# teensyMotors02_upSwitch.net
KiCad netlist of a schematic drawn in EAGLE
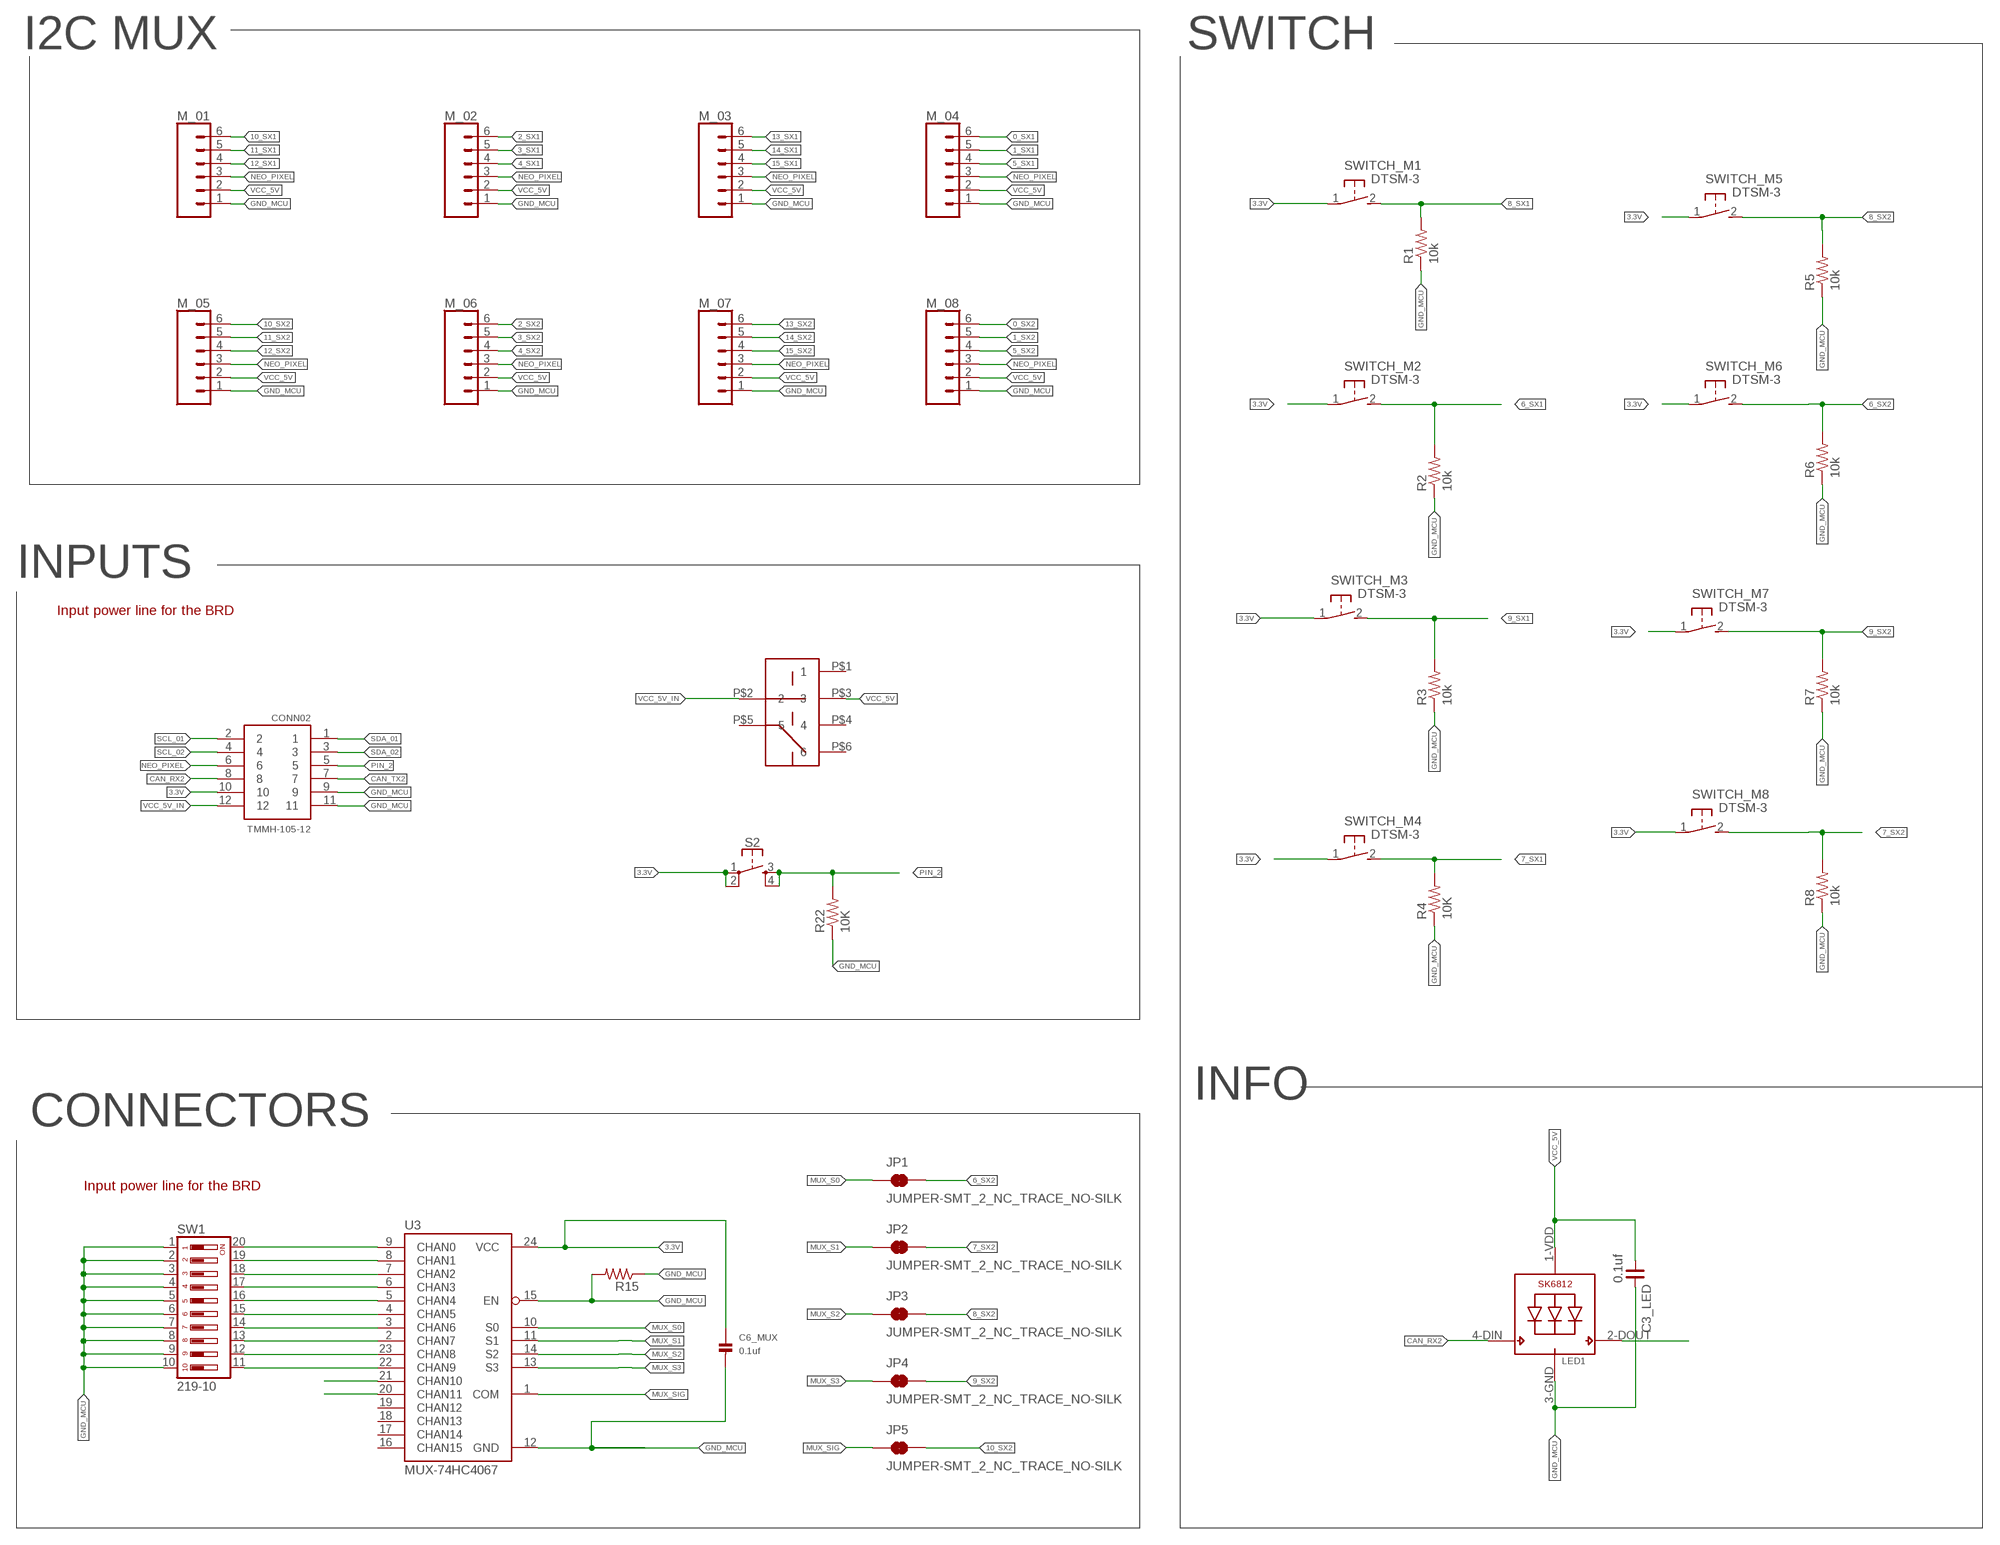
[diagram p0: schematic, sheet 1, part 1 of 2]
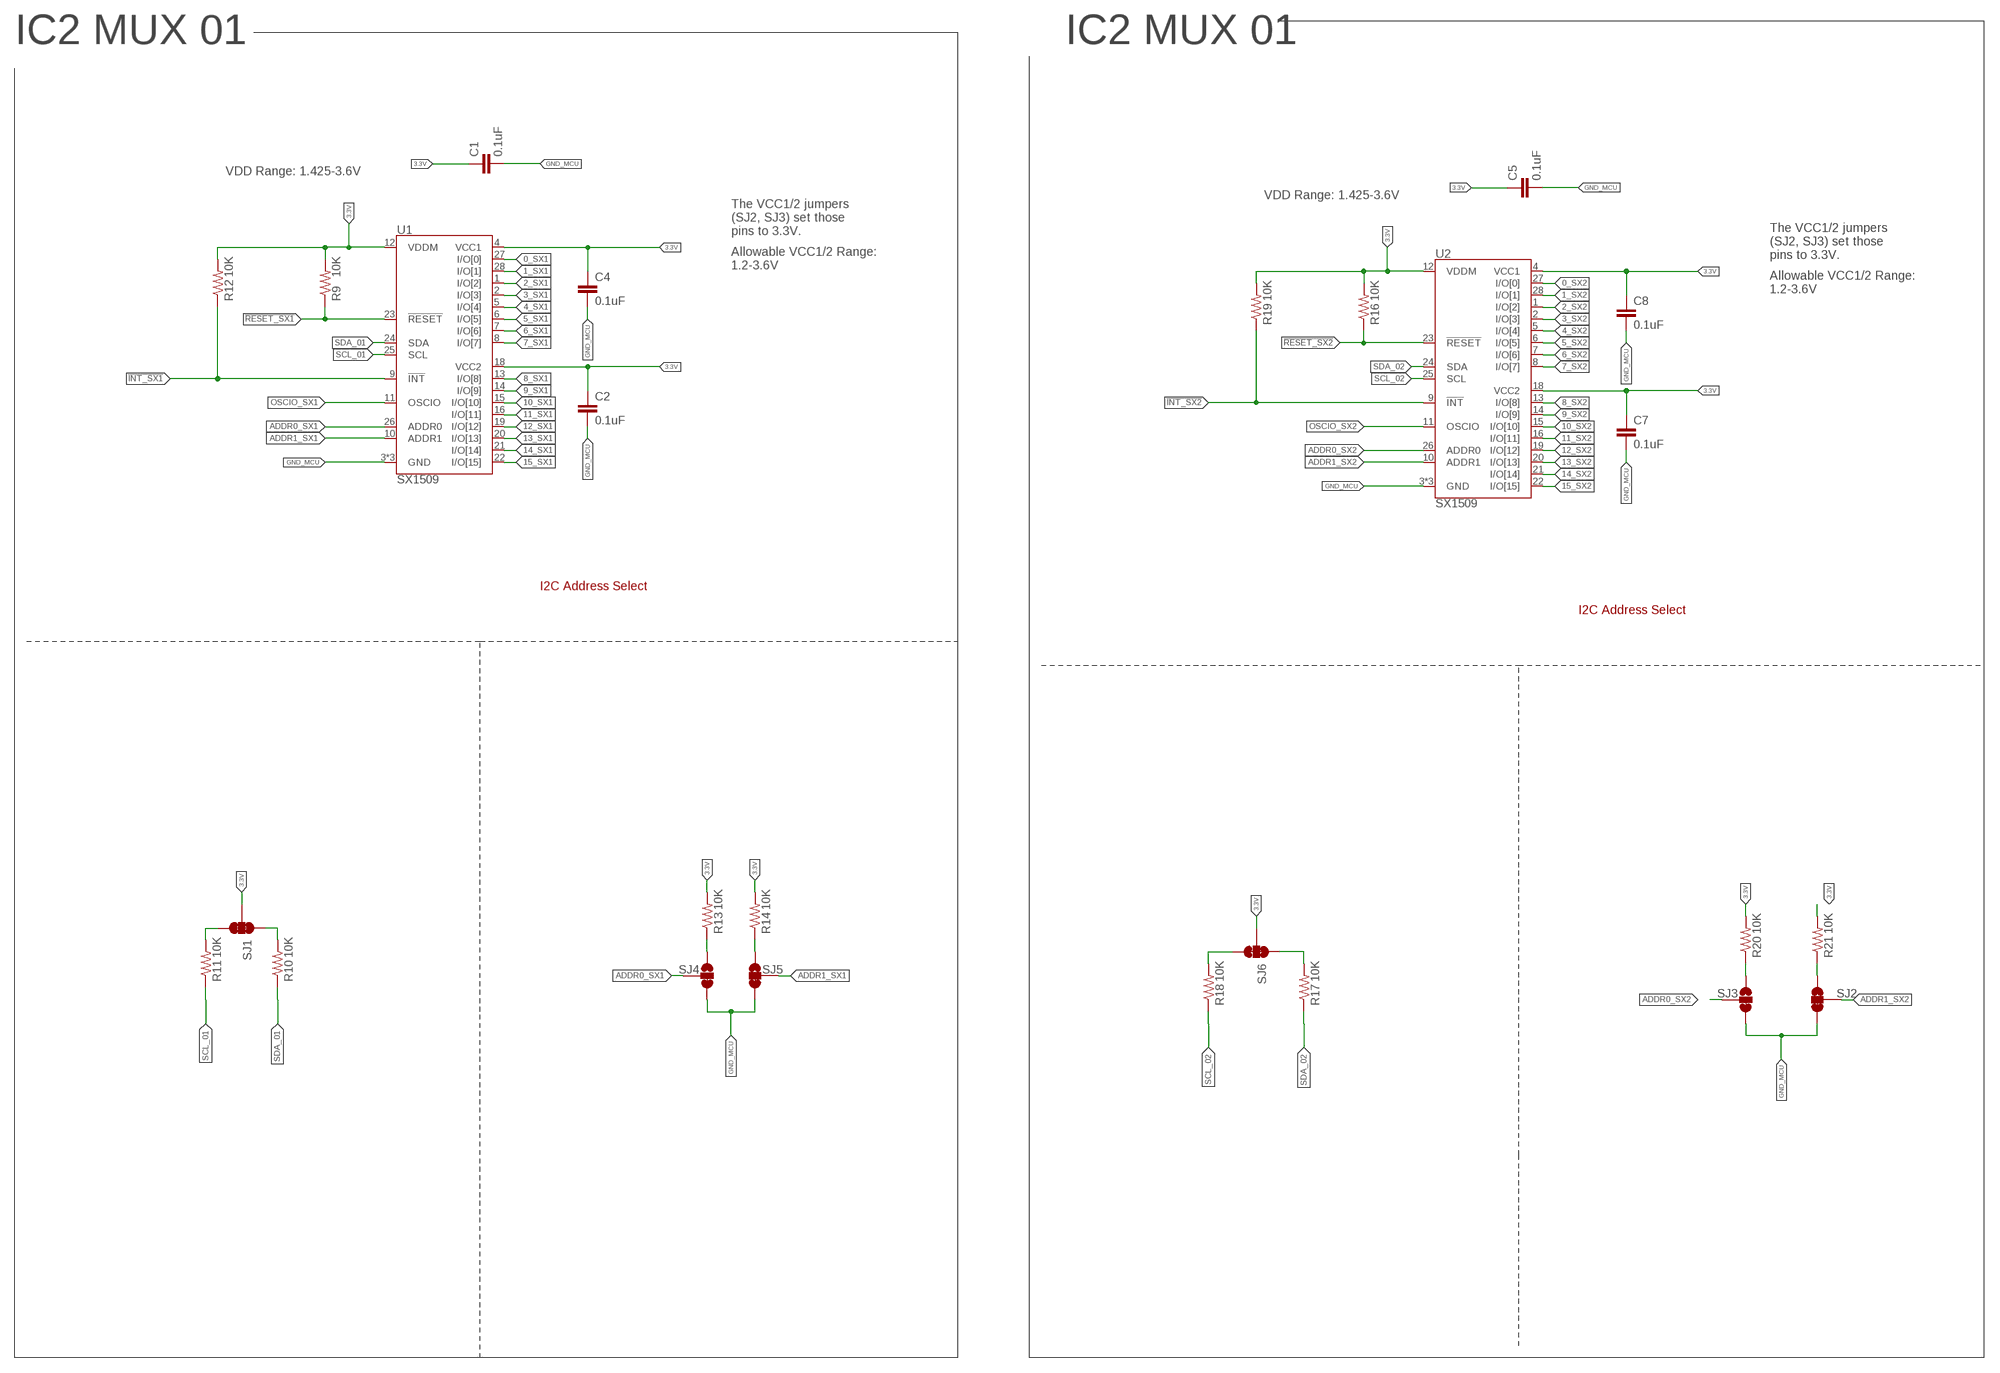
[diagram p1: schematic, sheet 1, part 2 of 2]

(export (version "E")
  (design (tool "Eeschema 10.0.6"))
  (components
    (comp (ref "C1")
      (value "0.1uF")
      (footprint "eagle-import:0603-CAP")
      (libsource (lib "eagle-import") (part "0.1UF-25V(+80/-20%)(0603)"))
    )
    (comp (ref "C2")
      (value "0.1uF")
      (footprint "eagle-import:0603-CAP")
      (libsource (lib "eagle-import") (part "0.1UF-25V(+80/-20%)(0603)"))
    )
    (comp (ref "C3_LED")
      (value "0.1uf")
      (footprint "eagle-import:C0805")
      (libsource (lib "eagle-import") (part "C_0805"))
    )
    (comp (ref "C4")
      (value "0.1uF")
      (footprint "eagle-import:0603-CAP")
      (libsource (lib "eagle-import") (part "0.1UF-25V(+80/-20%)(0603)"))
    )
    (comp (ref "C5")
      (value "0.1uF")
      (footprint "eagle-import:0603-CAP")
      (libsource (lib "eagle-import") (part "0.1UF-25V(+80/-20%)(0603)"))
    )
    (comp (ref "C6_MUX")
      (value "0.1uf")
      (footprint "eagle-import:0805")
      (libsource (lib "eagle-import") (part "CAP_CERAMIC0805"))
    )
    (comp (ref "C7")
      (value "0.1uF")
      (footprint "eagle-import:0603-CAP")
      (libsource (lib "eagle-import") (part "0.1UF-25V(+80/-20%)(0603)"))
    )
    (comp (ref "C8")
      (value "0.1uF")
      (footprint "eagle-import:0603-CAP")
      (libsource (lib "eagle-import") (part "0.1UF-25V(+80/-20%)(0603)"))
    )
    (comp (ref "CONN02")
      (value "TMMH-105-12")
      (footprint "eagle-import:TMMH-105-12")
      (libsource (lib "eagle-import") (part "TMMH-105-12"))
    )
    (comp (ref "JP1")
      (value "JUMPER-SMT_2_NC_TRACE_NO-SILK")
      (footprint "eagle-import:SMT-JUMPER_2_NC_TRACE_NO-SILK")
      (libsource (lib "eagle-import") (part "JUMPER-SMT_2_NC_TRACE_NO-SILK"))
    )
    (comp (ref "JP2")
      (value "JUMPER-SMT_2_NC_TRACE_NO-SILK")
      (footprint "eagle-import:SMT-JUMPER_2_NC_TRACE_NO-SILK")
      (libsource (lib "eagle-import") (part "JUMPER-SMT_2_NC_TRACE_NO-SILK"))
    )
    (comp (ref "JP3")
      (value "JUMPER-SMT_2_NC_TRACE_NO-SILK")
      (footprint "eagle-import:SMT-JUMPER_2_NC_TRACE_NO-SILK")
      (libsource (lib "eagle-import") (part "JUMPER-SMT_2_NC_TRACE_NO-SILK"))
    )
    (comp (ref "JP4")
      (value "JUMPER-SMT_2_NC_TRACE_NO-SILK")
      (footprint "eagle-import:SMT-JUMPER_2_NC_TRACE_NO-SILK")
      (libsource (lib "eagle-import") (part "JUMPER-SMT_2_NC_TRACE_NO-SILK"))
    )
    (comp (ref "JP5")
      (value "JUMPER-SMT_2_NC_TRACE_NO-SILK")
      (footprint "eagle-import:SMT-JUMPER_2_NC_TRACE_NO-SILK")
      (libsource (lib "eagle-import") (part "JUMPER-SMT_2_NC_TRACE_NO-SILK"))
    )
    (comp (ref "LED1")
      (value "SK6812_5050N")
      (footprint "eagle-import:LED5050_N")
      (libsource (lib "eagle-import") (part "SK6812_5050N"))
    )
    (comp (ref "M_01")
      (value "CONN_06SMD-1MM")
      (footprint "eagle-import:1X06-1MM")
      (libsource (lib "eagle-import") (part "CONN_06SMD-1MM"))
    )
    (comp (ref "M_02")
      (value "CONN_06SMD-1MM")
      (footprint "eagle-import:1X06-1MM")
      (libsource (lib "eagle-import") (part "CONN_06SMD-1MM"))
    )
    (comp (ref "M_03")
      (value "CONN_06SMD-1MM")
      (footprint "eagle-import:1X06-1MM")
      (libsource (lib "eagle-import") (part "CONN_06SMD-1MM"))
    )
    (comp (ref "M_04")
      (value "CONN_06SMD-1MM")
      (footprint "eagle-import:1X06-1MM")
      (libsource (lib "eagle-import") (part "CONN_06SMD-1MM"))
    )
    (comp (ref "M_05")
      (value "CONN_06SMD-1MM")
      (footprint "eagle-import:1X06-1MM")
      (libsource (lib "eagle-import") (part "CONN_06SMD-1MM"))
    )
    (comp (ref "M_06")
      (value "CONN_06SMD-1MM")
      (footprint "eagle-import:1X06-1MM")
      (libsource (lib "eagle-import") (part "CONN_06SMD-1MM"))
    )
    (comp (ref "M_07")
      (value "CONN_06SMD-1MM")
      (footprint "eagle-import:1X06-1MM")
      (libsource (lib "eagle-import") (part "CONN_06SMD-1MM"))
    )
    (comp (ref "M_08")
      (value "CONN_06SMD-1MM")
      (footprint "eagle-import:1X06-1MM")
      (libsource (lib "eagle-import") (part "CONN_06SMD-1MM"))
    )
    (comp (ref "R1")
      (value "10k")
      (footprint "eagle-import:M0805")
      (libsource (lib "eagle-import") (part "R-US_M0805"))
    )
    (comp (ref "R2")
      (value "10k")
      (footprint "eagle-import:M0805")
      (libsource (lib "eagle-import") (part "R-US_M0805"))
    )
    (comp (ref "R3")
      (value "10k")
      (footprint "eagle-import:M0805")
      (libsource (lib "eagle-import") (part "R-US_M0805"))
    )
    (comp (ref "R4")
      (value "10K")
      (footprint "eagle-import:M0805")
      (libsource (lib "eagle-import") (part "R-US_M0805"))
    )
    (comp (ref "R5")
      (value "10k")
      (footprint "eagle-import:M0805")
      (libsource (lib "eagle-import") (part "R-US_M0805"))
    )
    (comp (ref "R6")
      (value "10k")
      (footprint "eagle-import:M0805")
      (libsource (lib "eagle-import") (part "R-US_M0805"))
    )
    (comp (ref "R7")
      (value "10k")
      (footprint "eagle-import:M0805")
      (libsource (lib "eagle-import") (part "R-US_M0805"))
    )
    (comp (ref "R8")
      (value "10k")
      (footprint "eagle-import:M0805")
      (libsource (lib "eagle-import") (part "R-US_M0805"))
    )
    (comp (ref "R9")
      (value "10K")
      (footprint "eagle-import:0603-RES")
      (libsource (lib "eagle-import") (part "10KOHM-1/10W-1%(0603)0603"))
    )
    (comp (ref "R10")
      (value "10K")
      (footprint "eagle-import:0603-RES")
      (libsource (lib "eagle-import") (part "10KOHM-1/10W-1%(0603)0603"))
    )
    (comp (ref "R11")
      (value "10K")
      (footprint "eagle-import:0603-RES")
      (libsource (lib "eagle-import") (part "10KOHM-1/10W-1%(0603)0603"))
    )
    (comp (ref "R12")
      (value "10K")
      (footprint "eagle-import:0603-RES")
      (libsource (lib "eagle-import") (part "10KOHM-1/10W-1%(0603)0603"))
    )
    (comp (ref "R13")
      (value "10K")
      (footprint "eagle-import:0603-RES")
      (libsource (lib "eagle-import") (part "10KOHM-1/10W-1%(0603)0603"))
    )
    (comp (ref "R14")
      (value "10K")
      (footprint "eagle-import:0603-RES")
      (libsource (lib "eagle-import") (part "10KOHM-1/10W-1%(0603)0603"))
    )
    (comp (ref "R15")
      (value "R-US_M0805")
      (footprint "eagle-import:M0805")
      (libsource (lib "eagle-import") (part "R-US_M0805"))
    )
    (comp (ref "R16")
      (value "10K")
      (footprint "eagle-import:0603-RES")
      (libsource (lib "eagle-import") (part "10KOHM-1/10W-1%(0603)0603"))
    )
    (comp (ref "R17")
      (value "10K")
      (footprint "eagle-import:0603-RES")
      (libsource (lib "eagle-import") (part "10KOHM-1/10W-1%(0603)0603"))
    )
    (comp (ref "R18")
      (value "10K")
      (footprint "eagle-import:0603-RES")
      (libsource (lib "eagle-import") (part "10KOHM-1/10W-1%(0603)0603"))
    )
    (comp (ref "R19")
      (value "10K")
      (footprint "eagle-import:0603-RES")
      (libsource (lib "eagle-import") (part "10KOHM-1/10W-1%(0603)0603"))
    )
    (comp (ref "R20")
      (value "10K")
      (footprint "eagle-import:0603-RES")
      (libsource (lib "eagle-import") (part "10KOHM-1/10W-1%(0603)0603"))
    )
    (comp (ref "R21")
      (value "10K")
      (footprint "eagle-import:0603-RES")
      (libsource (lib "eagle-import") (part "10KOHM-1/10W-1%(0603)0603"))
    )
    (comp (ref "R22")
      (value "10K")
      (footprint "eagle-import:M0805")
      (libsource (lib "eagle-import") (part "R-US_M0805"))
    )
    (comp (ref "S2")
      (value "MOMENTARY-SWITCH-SPST-2-SMD-5.2MM")
      (footprint "eagle-import:TACTILE_SWITCH_SMD_5.2MM")
      (libsource (lib "eagle-import") (part "MOMENTARY-SWITCH-SPST-2-SMD-5.2MM"))
    )
    (comp (ref "SJ1")
      (value "JUMPER-PAD-3-NC_BY_TRACE")
      (footprint "eagle-import:PAD-JUMPER-3-3OF3_NC_BY_TRACE_YES_SILK_FULL_BOX")
      (libsource (lib "eagle-import") (part "JUMPER-PAD-3-NC_BY_TRACE"))
    )
    (comp (ref "SJ2")
      (value "JUMPER-PAD-3-2OF3_NC_BY_TRACE_SMALL")
      (footprint "eagle-import:PAD-JUMPER-3-2OF3_NC_BY_TRACE_YES_SILK_FULL_BOX")
      (libsource (lib "eagle-import") (part "JUMPER-PAD-3-2OF3_NC_BY_TRACE_SMALL"))
    )
    (comp (ref "SJ3")
      (value "JUMPER-PAD-3-2OF3_NC_BY_TRACE_SMALL")
      (footprint "eagle-import:PAD-JUMPER-3-2OF3_NC_BY_TRACE_YES_SILK_FULL_BOX")
      (libsource (lib "eagle-import") (part "JUMPER-PAD-3-2OF3_NC_BY_TRACE_SMALL"))
    )
    (comp (ref "SJ4")
      (value "JUMPER-PAD-3-2OF3_NC_BY_TRACE_SMALL")
      (footprint "eagle-import:PAD-JUMPER-3-2OF3_NC_BY_TRACE_YES_SILK_FULL_BOX")
      (libsource (lib "eagle-import") (part "JUMPER-PAD-3-2OF3_NC_BY_TRACE_SMALL"))
    )
    (comp (ref "SJ5")
      (value "JUMPER-PAD-3-2OF3_NC_BY_TRACE_SMALL")
      (footprint "eagle-import:PAD-JUMPER-3-2OF3_NC_BY_TRACE_YES_SILK_FULL_BOX")
      (libsource (lib "eagle-import") (part "JUMPER-PAD-3-2OF3_NC_BY_TRACE_SMALL"))
    )
    (comp (ref "SJ6")
      (value "JUMPER-PAD-3-NC_BY_TRACE")
      (footprint "eagle-import:PAD-JUMPER-3-3OF3_NC_BY_TRACE_YES_SILK_FULL_BOX")
      (libsource (lib "eagle-import") (part "JUMPER-PAD-3-NC_BY_TRACE"))
    )
    (comp (ref "SW1")
      (value "219-10")
      (footprint "eagle-import:CTS-219-10")
      (fields (field (name "MF") "SLI (CML/IDI)") (field (name "MPN") "219-10PK"))
      (libsource (lib "eagle-import") (part "219-10"))
    )
    (comp (ref "SWITCH_M1")
      (value "DTSM-3")
      (footprint "eagle-import:DTSM-3")
      (libsource (lib "eagle-import") (part "DTSM-3"))
    )
    (comp (ref "SWITCH_M2")
      (value "DTSM-3")
      (footprint "eagle-import:DTSM-3")
      (libsource (lib "eagle-import") (part "DTSM-3"))
    )
    (comp (ref "SWITCH_M3")
      (value "DTSM-3")
      (footprint "eagle-import:DTSM-3")
      (libsource (lib "eagle-import") (part "DTSM-3"))
    )
    (comp (ref "SWITCH_M4")
      (value "DTSM-3")
      (footprint "eagle-import:DTSM-3")
      (libsource (lib "eagle-import") (part "DTSM-3"))
    )
    (comp (ref "SWITCH_M5")
      (value "DTSM-3")
      (footprint "eagle-import:DTSM-3")
      (libsource (lib "eagle-import") (part "DTSM-3"))
    )
    (comp (ref "SWITCH_M6")
      (value "DTSM-3")
      (footprint "eagle-import:DTSM-3")
      (libsource (lib "eagle-import") (part "DTSM-3"))
    )
    (comp (ref "SWITCH_M7")
      (value "DTSM-3")
      (footprint "eagle-import:DTSM-3")
      (libsource (lib "eagle-import") (part "DTSM-3"))
    )
    (comp (ref "SWITCH_M8")
      (value "DTSM-3")
      (footprint "eagle-import:DTSM-3")
      (libsource (lib "eagle-import") (part "DTSM-3"))
    )
    (comp (ref "U$1")
      (value "MFS201N－9－Z")
      (footprint "eagle-import:MFS201N－9－Z")
      (libsource (lib "eagle-import") (part "MFS201N－9－Z"))
    )
    (comp (ref "U1")
      (value "SX1509")
      (footprint "eagle-import:QFN-28")
      (libsource (lib "eagle-import") (part "SX1509"))
    )
    (comp (ref "U2")
      (value "SX1509")
      (footprint "eagle-import:QFN-28")
      (libsource (lib "eagle-import") (part "SX1509"))
    )
    (comp (ref "U3")
      (value "MUX-74HC4067")
      (footprint "eagle-import:SSOP24")
      (libsource (lib "eagle-import") (part "MUX-74HC4067SMD"))
    )
  )
  (nets
    (net (code "1") (name "/~{INT_SX1}") (class "Default")
      (node (ref "R12") (pin "1") (pinfunction "1_1") (pintype "passive"))
      (node (ref "U1") (pin "9") (pinfunction "~{INT}_9") (pintype "bidirectional"))
    )
    (net (code "2") (name "/~{INT_SX2}") (class "Default")
      (node (ref "R19") (pin "1") (pinfunction "1_1") (pintype "passive"))
      (node (ref "U2") (pin "9") (pinfunction "~{INT}_9") (pintype "bidirectional"))
    )
    (net (code "3") (name "/~{RESET_SX1}") (class "Default")
      (node (ref "R9") (pin "1") (pinfunction "1_1") (pintype "passive"))
      (node (ref "U1") (pin "23") (pinfunction "~{RESET}_23") (pintype "bidirectional"))
    )
    (net (code "4") (name "/~{RESET_SX2}") (class "Default")
      (node (ref "R16") (pin "1") (pinfunction "1_1") (pintype "passive"))
      (node (ref "U2") (pin "23") (pinfunction "~{RESET}_23") (pintype "bidirectional"))
    )
    (net (code "5") (name "0_SX1") (class "Default")
      (node (ref "M_04") (pin "6") (pinfunction "6_6") (pintype "passive"))
      (node (ref "U1") (pin "27") (pinfunction "I/O[0]_27") (pintype "bidirectional"))
    )
    (net (code "6") (name "0_SX2") (class "Default")
      (node (ref "M_08") (pin "6") (pinfunction "6_6") (pintype "passive"))
      (node (ref "U2") (pin "27") (pinfunction "I/O[0]_27") (pintype "bidirectional"))
    )
    (net (code "7") (name "1_SX1") (class "Default")
      (node (ref "M_04") (pin "5") (pinfunction "5_5") (pintype "passive"))
      (node (ref "U1") (pin "28") (pinfunction "I/O[1]_28") (pintype "bidirectional"))
    )
    (net (code "8") (name "1_SX2") (class "Default")
      (node (ref "M_08") (pin "5") (pinfunction "5_5") (pintype "passive"))
      (node (ref "U2") (pin "28") (pinfunction "I/O[1]_28") (pintype "bidirectional"))
    )
    (net (code "9") (name "2_SX1") (class "Default")
      (node (ref "M_02") (pin "6") (pinfunction "6_6") (pintype "passive"))
      (node (ref "U1") (pin "1") (pinfunction "I/O[2]_1") (pintype "bidirectional"))
    )
    (net (code "10") (name "2_SX2") (class "Default")
      (node (ref "M_06") (pin "6") (pinfunction "6_6") (pintype "passive"))
      (node (ref "U2") (pin "1") (pinfunction "I/O[2]_1") (pintype "bidirectional"))
    )
    (net (code "11") (name "3.3V") (class "Default")
      (node (ref "C1") (pin "1") (pinfunction "1_1") (pintype "passive"))
      (node (ref "C2") (pin "1") (pinfunction "1_1") (pintype "passive"))
      (node (ref "C4") (pin "1") (pinfunction "1_1") (pintype "passive"))
      (node (ref "C5") (pin "1") (pinfunction "1_1") (pintype "passive"))
      (node (ref "C6_MUX") (pin "1") (pinfunction "P$1_1") (pintype "passive"))
      (node (ref "C7") (pin "1") (pinfunction "1_1") (pintype "passive"))
      (node (ref "C8") (pin "1") (pinfunction "1_1") (pintype "passive"))
      (node (ref "CONN02") (pin "10") (pinfunction "10_10") (pintype "bidirectional"))
      (node (ref "R12") (pin "2") (pinfunction "2_2") (pintype "passive"))
      (node (ref "R13") (pin "2") (pinfunction "2_2") (pintype "passive"))
      (node (ref "R14") (pin "2") (pinfunction "2_2") (pintype "passive"))
      (node (ref "R16") (pin "2") (pinfunction "2_2") (pintype "passive"))
      (node (ref "R19") (pin "2") (pinfunction "2_2") (pintype "passive"))
      (node (ref "R20") (pin "2") (pinfunction "2_2") (pintype "passive"))
      (node (ref "R21") (pin "2") (pinfunction "2_2") (pintype "passive"))
      (node (ref "R9") (pin "2") (pinfunction "2_2") (pintype "passive"))
      (node (ref "S2") (pin "1") (pinfunction "1_1") (pintype "passive"))
      (node (ref "S2") (pin "2") (pinfunction "2_2") (pintype "passive"))
      (node (ref "SJ1") (pin "2") (pinfunction "2_2") (pintype "passive"))
      (node (ref "SJ6") (pin "2") (pinfunction "2_2") (pintype "passive"))
      (node (ref "SWITCH_M1") (pin "1") (pinfunction "1_1") (pintype "passive"))
      (node (ref "SWITCH_M2") (pin "1") (pinfunction "1_1") (pintype "passive"))
      (node (ref "SWITCH_M3") (pin "1") (pinfunction "1_1") (pintype "passive"))
      (node (ref "SWITCH_M4") (pin "1") (pinfunction "1_1") (pintype "passive"))
      (node (ref "SWITCH_M5") (pin "1") (pinfunction "1_1") (pintype "passive"))
      (node (ref "SWITCH_M6") (pin "1") (pinfunction "1_1") (pintype "passive"))
      (node (ref "SWITCH_M7") (pin "1") (pinfunction "1_1") (pintype "passive"))
      (node (ref "SWITCH_M8") (pin "1") (pinfunction "1_1") (pintype "passive"))
      (node (ref "U1") (pin "12") (pinfunction "VDDM_12") (pintype "bidirectional"))
      (node (ref "U1") (pin "18") (pinfunction "VCC2_18") (pintype "bidirectional"))
      (node (ref "U1") (pin "4") (pinfunction "VCC1_4") (pintype "bidirectional"))
      (node (ref "U2") (pin "12") (pinfunction "VDDM_12") (pintype "bidirectional"))
      (node (ref "U2") (pin "18") (pinfunction "VCC2_18") (pintype "bidirectional"))
      (node (ref "U2") (pin "4") (pinfunction "VCC1_4") (pintype "bidirectional"))
      (node (ref "U3") (pin "24") (pinfunction "VCC_24") (pintype "bidirectional"))
    )
    (net (code "12") (name "3_SX1") (class "Default")
      (node (ref "M_02") (pin "5") (pinfunction "5_5") (pintype "passive"))
      (node (ref "U1") (pin "2") (pinfunction "I/O[3]_2") (pintype "bidirectional"))
    )
    (net (code "13") (name "3_SX2") (class "Default")
      (node (ref "M_06") (pin "5") (pinfunction "5_5") (pintype "passive"))
      (node (ref "U2") (pin "2") (pinfunction "I/O[3]_2") (pintype "bidirectional"))
    )
    (net (code "14") (name "4_SX1") (class "Default")
      (node (ref "M_02") (pin "4") (pinfunction "4_4") (pintype "passive"))
      (node (ref "U1") (pin "5") (pinfunction "I/O[4]_5") (pintype "bidirectional"))
    )
    (net (code "15") (name "4_SX2") (class "Default")
      (node (ref "M_06") (pin "4") (pinfunction "4_4") (pintype "passive"))
      (node (ref "U2") (pin "5") (pinfunction "I/O[4]_5") (pintype "bidirectional"))
    )
    (net (code "16") (name "5_SX1") (class "Default")
      (node (ref "M_04") (pin "4") (pinfunction "4_4") (pintype "passive"))
      (node (ref "U1") (pin "6") (pinfunction "I/O[5]_6") (pintype "bidirectional"))
    )
    (net (code "17") (name "5_SX2") (class "Default")
      (node (ref "M_08") (pin "4") (pinfunction "4_4") (pintype "passive"))
      (node (ref "U2") (pin "6") (pinfunction "I/O[5]_6") (pintype "bidirectional"))
    )
    (net (code "18") (name "6_SX1") (class "Default")
      (node (ref "R2") (pin "2") (pinfunction "2_2") (pintype "passive"))
      (node (ref "SWITCH_M2") (pin "2") (pinfunction "2_2") (pintype "passive"))
      (node (ref "U1") (pin "7") (pinfunction "I/O[6]_7") (pintype "bidirectional"))
    )
    (net (code "19") (name "6_SX2") (class "Default")
      (node (ref "JP1") (pin "2") (pinfunction "2_2") (pintype "passive"))
      (node (ref "R6") (pin "2") (pinfunction "2_2") (pintype "passive"))
      (node (ref "SWITCH_M6") (pin "2") (pinfunction "2_2") (pintype "passive"))
      (node (ref "U2") (pin "7") (pinfunction "I/O[6]_7") (pintype "bidirectional"))
    )
    (net (code "20") (name "7_SX1") (class "Default")
      (node (ref "R4") (pin "2") (pinfunction "2_2") (pintype "passive"))
      (node (ref "SWITCH_M4") (pin "2") (pinfunction "2_2") (pintype "passive"))
      (node (ref "U1") (pin "8") (pinfunction "I/O[7]_8") (pintype "bidirectional"))
    )
    (net (code "21") (name "7_SX2") (class "Default")
      (node (ref "JP2") (pin "2") (pinfunction "2_2") (pintype "passive"))
      (node (ref "R8") (pin "2") (pinfunction "2_2") (pintype "passive"))
      (node (ref "SWITCH_M8") (pin "2") (pinfunction "2_2") (pintype "passive"))
      (node (ref "U2") (pin "8") (pinfunction "I/O[7]_8") (pintype "bidirectional"))
    )
    (net (code "22") (name "8_SX1") (class "Default")
      (node (ref "R1") (pin "2") (pinfunction "2_2") (pintype "passive"))
      (node (ref "SWITCH_M1") (pin "2") (pinfunction "2_2") (pintype "passive"))
      (node (ref "U1") (pin "13") (pinfunction "I/O[8]_13") (pintype "bidirectional"))
    )
    (net (code "23") (name "8_SX2") (class "Default")
      (node (ref "JP3") (pin "2") (pinfunction "2_2") (pintype "passive"))
      (node (ref "R5") (pin "2") (pinfunction "2_2") (pintype "passive"))
      (node (ref "SWITCH_M5") (pin "2") (pinfunction "2_2") (pintype "passive"))
      (node (ref "U2") (pin "13") (pinfunction "I/O[8]_13") (pintype "bidirectional"))
    )
    (net (code "24") (name "9_SX1") (class "Default")
      (node (ref "R3") (pin "2") (pinfunction "2_2") (pintype "passive"))
      (node (ref "SWITCH_M3") (pin "2") (pinfunction "2_2") (pintype "passive"))
      (node (ref "U1") (pin "14") (pinfunction "I/O[9]_14") (pintype "bidirectional"))
    )
    (net (code "25") (name "9_SX2") (class "Default")
      (node (ref "JP4") (pin "2") (pinfunction "2_2") (pintype "passive"))
      (node (ref "R7") (pin "2") (pinfunction "2_2") (pintype "passive"))
      (node (ref "SWITCH_M7") (pin "2") (pinfunction "2_2") (pintype "passive"))
      (node (ref "U2") (pin "14") (pinfunction "I/O[9]_14") (pintype "bidirectional"))
    )
    (net (code "26") (name "10_SX1") (class "Default")
      (node (ref "M_01") (pin "6") (pinfunction "6_6") (pintype "passive"))
      (node (ref "U1") (pin "15") (pinfunction "I/O[10]_15") (pintype "bidirectional"))
    )
    (net (code "27") (name "10_SX2") (class "Default")
      (node (ref "JP5") (pin "2") (pinfunction "2_2") (pintype "passive"))
      (node (ref "M_05") (pin "6") (pinfunction "6_6") (pintype "passive"))
      (node (ref "U2") (pin "15") (pinfunction "I/O[10]_15") (pintype "bidirectional"))
    )
    (net (code "28") (name "11_SX1") (class "Default")
      (node (ref "M_01") (pin "5") (pinfunction "5_5") (pintype "passive"))
      (node (ref "U1") (pin "16") (pinfunction "I/O[11]_16") (pintype "bidirectional"))
    )
    (net (code "29") (name "11_SX2") (class "Default")
      (node (ref "M_05") (pin "5") (pinfunction "5_5") (pintype "passive"))
      (node (ref "U2") (pin "16") (pinfunction "I/O[11]_16") (pintype "bidirectional"))
    )
    (net (code "30") (name "12_SX1") (class "Default")
      (node (ref "M_01") (pin "4") (pinfunction "4_4") (pintype "passive"))
      (node (ref "U1") (pin "19") (pinfunction "I/O[12]_19") (pintype "bidirectional"))
    )
    (net (code "31") (name "12_SX2") (class "Default")
      (node (ref "M_05") (pin "4") (pinfunction "4_4") (pintype "passive"))
      (node (ref "U2") (pin "19") (pinfunction "I/O[12]_19") (pintype "bidirectional"))
    )
    (net (code "32") (name "13_SX1") (class "Default")
      (node (ref "M_03") (pin "6") (pinfunction "6_6") (pintype "passive"))
      (node (ref "U1") (pin "20") (pinfunction "I/O[13]_20") (pintype "bidirectional"))
    )
    (net (code "33") (name "13_SX2") (class "Default")
      (node (ref "M_07") (pin "6") (pinfunction "6_6") (pintype "passive"))
      (node (ref "U2") (pin "20") (pinfunction "I/O[13]_20") (pintype "bidirectional"))
    )
    (net (code "34") (name "14_SX1") (class "Default")
      (node (ref "M_03") (pin "5") (pinfunction "5_5") (pintype "passive"))
      (node (ref "U1") (pin "21") (pinfunction "I/O[14]_21") (pintype "bidirectional"))
    )
    (net (code "35") (name "14_SX2") (class "Default")
      (node (ref "M_07") (pin "5") (pinfunction "5_5") (pintype "passive"))
      (node (ref "U2") (pin "21") (pinfunction "I/O[14]_21") (pintype "bidirectional"))
    )
    (net (code "36") (name "15_SX1") (class "Default")
      (node (ref "M_03") (pin "4") (pinfunction "4_4") (pintype "passive"))
      (node (ref "U1") (pin "22") (pinfunction "I/O[15]_22") (pintype "bidirectional"))
    )
    (net (code "37") (name "15_SX2") (class "Default")
      (node (ref "M_07") (pin "4") (pinfunction "4_4") (pintype "passive"))
      (node (ref "U2") (pin "22") (pinfunction "I/O[15]_22") (pintype "bidirectional"))
    )
    (net (code "38") (name "ADDR0_SX1") (class "Default")
      (node (ref "SJ4") (pin "2") (pinfunction "2_2") (pintype "passive"))
      (node (ref "U1") (pin "26") (pinfunction "ADDR0_26") (pintype "bidirectional"))
    )
    (net (code "39") (name "ADDR0_SX2") (class "Default")
      (node (ref "SJ3") (pin "2") (pinfunction "2_2") (pintype "passive"))
      (node (ref "U2") (pin "26") (pinfunction "ADDR0_26") (pintype "bidirectional"))
    )
    (net (code "40") (name "ADDR1_SX1") (class "Default")
      (node (ref "SJ5") (pin "2") (pinfunction "2_2") (pintype "passive"))
      (node (ref "U1") (pin "10") (pinfunction "ADDR1_10") (pintype "bidirectional"))
    )
    (net (code "41") (name "ADDR1_SX2") (class "Default")
      (node (ref "SJ2") (pin "2") (pinfunction "2_2") (pintype "passive"))
      (node (ref "U2") (pin "10") (pinfunction "ADDR1_10") (pintype "bidirectional"))
    )
    (net (code "42") (name "CAN_RX2") (class "Default")
      (node (ref "CONN02") (pin "8") (pinfunction "8_8") (pintype "bidirectional"))
      (node (ref "LED1") (pin "4-DIN") (pinfunction "DI_4-DIN") (pintype "input"))
    )
    (net (code "43") (name "CAN_TX2") (class "Default")
      (node (ref "CONN02") (pin "7") (pinfunction "7_7") (pintype "bidirectional"))
    )
    (net (code "44") (name "GND_MCU") (class "Default")
      (node (ref "C1") (pin "2") (pinfunction "2_2") (pintype "passive"))
      (node (ref "C2") (pin "2") (pinfunction "2_2") (pintype "passive"))
      (node (ref "C3_LED") (pin "2") (pinfunction "2_2") (pintype "passive"))
      (node (ref "C4") (pin "2") (pinfunction "2_2") (pintype "passive"))
      (node (ref "C5") (pin "2") (pinfunction "2_2") (pintype "passive"))
      (node (ref "C6_MUX") (pin "2") (pinfunction "P$2_2") (pintype "passive"))
      (node (ref "C7") (pin "2") (pinfunction "2_2") (pintype "passive"))
      (node (ref "C8") (pin "2") (pinfunction "2_2") (pintype "passive"))
      (node (ref "CONN02") (pin "11") (pinfunction "11_11") (pintype "bidirectional"))
      (node (ref "CONN02") (pin "9") (pinfunction "9_9") (pintype "bidirectional"))
      (node (ref "LED1") (pin "3-GND") (pinfunction "GND_3-GND") (pintype "power_in"))
      (node (ref "M_01") (pin "1") (pinfunction "1_1") (pintype "passive"))
      (node (ref "M_02") (pin "1") (pinfunction "1_1") (pintype "passive"))
      (node (ref "M_03") (pin "1") (pinfunction "1_1") (pintype "passive"))
      (node (ref "M_04") (pin "1") (pinfunction "1_1") (pintype "passive"))
      (node (ref "M_05") (pin "1") (pinfunction "1_1") (pintype "passive"))
      (node (ref "M_06") (pin "1") (pinfunction "1_1") (pintype "passive"))
      (node (ref "M_07") (pin "1") (pinfunction "1_1") (pintype "passive"))
      (node (ref "M_08") (pin "1") (pinfunction "1_1") (pintype "passive"))
      (node (ref "R1") (pin "1") (pinfunction "1_1") (pintype "passive"))
      (node (ref "R15") (pin "1") (pinfunction "1_1") (pintype "passive"))
      (node (ref "R15") (pin "2") (pinfunction "2_2") (pintype "passive"))
      (node (ref "R2") (pin "1") (pinfunction "1_1") (pintype "passive"))
      (node (ref "R22") (pin "1") (pinfunction "1_1") (pintype "passive"))
      (node (ref "R3") (pin "1") (pinfunction "1_1") (pintype "passive"))
      (node (ref "R4") (pin "1") (pinfunction "1_1") (pintype "passive"))
      (node (ref "R5") (pin "1") (pinfunction "1_1") (pintype "passive"))
      (node (ref "R6") (pin "1") (pinfunction "1_1") (pintype "passive"))
      (node (ref "R7") (pin "1") (pinfunction "1_1") (pintype "passive"))
      (node (ref "R8") (pin "1") (pinfunction "1_1") (pintype "passive"))
      (node (ref "SJ2") (pin "3") (pinfunction "3_3") (pintype "passive"))
      (node (ref "SJ3") (pin "3") (pinfunction "3_3") (pintype "passive"))
      (node (ref "SJ4") (pin "3") (pinfunction "3_3") (pintype "passive"))
      (node (ref "SJ5") (pin "3") (pinfunction "3_3") (pintype "passive"))
      (node (ref "SW1") (pin "1") (pinfunction "1_1") (pintype "passive"))
      (node (ref "SW1") (pin "10") (pinfunction "10_10") (pintype "passive"))
      (node (ref "SW1") (pin "2") (pinfunction "2_2") (pintype "passive"))
      (node (ref "SW1") (pin "3") (pinfunction "3_3") (pintype "passive"))
      (node (ref "SW1") (pin "4") (pinfunction "4_4") (pintype "passive"))
      (node (ref "SW1") (pin "5") (pinfunction "5_5") (pintype "passive"))
      (node (ref "SW1") (pin "6") (pinfunction "6_6") (pintype "passive"))
      (node (ref "SW1") (pin "7") (pinfunction "7_7") (pintype "passive"))
      (node (ref "SW1") (pin "8") (pinfunction "8_8") (pintype "passive"))
      (node (ref "SW1") (pin "9") (pinfunction "9_9") (pintype "passive"))
      (node (ref "U1") (pin "17") (pinfunction "GND_17") (pintype "bidirectional"))
      (node (ref "U1") (pin "29") (pinfunction "GND_29") (pintype "bidirectional"))
      (node (ref "U1") (pin "3") (pinfunction "GND_3") (pintype "bidirectional"))
      (node (ref "U2") (pin "17") (pinfunction "GND_17") (pintype "bidirectional"))
      (node (ref "U2") (pin "29") (pinfunction "GND_29") (pintype "bidirectional"))
      (node (ref "U2") (pin "3") (pinfunction "GND_3") (pintype "bidirectional"))
      (node (ref "U3") (pin "12") (pinfunction "GND_12") (pintype "bidirectional"))
      (node (ref "U3") (pin "15") (pinfunction "EN_15") (pintype "input"))
    )
    (net (code "45") (name "MUX_S0") (class "Default")
      (node (ref "JP1") (pin "1") (pinfunction "1_1") (pintype "passive"))
      (node (ref "U3") (pin "10") (pinfunction "S0_10") (pintype "input"))
    )
    (net (code "46") (name "MUX_S1") (class "Default")
      (node (ref "JP2") (pin "1") (pinfunction "1_1") (pintype "passive"))
      (node (ref "U3") (pin "11") (pinfunction "S1_11") (pintype "input"))
    )
    (net (code "47") (name "MUX_S2") (class "Default")
      (node (ref "JP3") (pin "1") (pinfunction "1_1") (pintype "passive"))
      (node (ref "U3") (pin "14") (pinfunction "S2_14") (pintype "input"))
    )
    (net (code "48") (name "MUX_S3") (class "Default")
      (node (ref "JP4") (pin "1") (pinfunction "1_1") (pintype "passive"))
      (node (ref "U3") (pin "13") (pinfunction "S3_13") (pintype "input"))
    )
    (net (code "49") (name "MUX_SIG") (class "Default")
      (node (ref "JP5") (pin "1") (pinfunction "1_1") (pintype "passive"))
      (node (ref "U3") (pin "1") (pinfunction "COM_1") (pintype "bidirectional"))
    )
    (net (code "50") (name "NEO_PIXEL") (class "Default")
      (node (ref "CONN02") (pin "6") (pinfunction "6_6") (pintype "bidirectional"))
      (node (ref "M_01") (pin "3") (pinfunction "3_3") (pintype "passive"))
      (node (ref "M_02") (pin "3") (pinfunction "3_3") (pintype "passive"))
      (node (ref "M_03") (pin "3") (pinfunction "3_3") (pintype "passive"))
      (node (ref "M_04") (pin "3") (pinfunction "3_3") (pintype "passive"))
      (node (ref "M_05") (pin "3") (pinfunction "3_3") (pintype "passive"))
      (node (ref "M_06") (pin "3") (pinfunction "3_3") (pintype "passive"))
      (node (ref "M_07") (pin "3") (pinfunction "3_3") (pintype "passive"))
      (node (ref "M_08") (pin "3") (pinfunction "3_3") (pintype "passive"))
    )
    (net (code "51") (name "Net-(R10-Pad2)") (class "Default")
      (node (ref "R10") (pin "2") (pinfunction "2_2") (pintype "passive"))
      (node (ref "SJ1") (pin "1") (pinfunction "1_1") (pintype "passive"))
    )
    (net (code "52") (name "Net-(R11-Pad2)") (class "Default")
      (node (ref "R11") (pin "2") (pinfunction "2_2") (pintype "passive"))
      (node (ref "SJ1") (pin "3") (pinfunction "3_3") (pintype "passive"))
    )
    (net (code "53") (name "Net-(R13-Pad1)") (class "Default")
      (node (ref "R13") (pin "1") (pinfunction "1_1") (pintype "passive"))
      (node (ref "SJ4") (pin "1") (pinfunction "1_1") (pintype "passive"))
    )
    (net (code "54") (name "Net-(R14-Pad1)") (class "Default")
      (node (ref "R14") (pin "1") (pinfunction "1_1") (pintype "passive"))
      (node (ref "SJ5") (pin "1") (pinfunction "1_1") (pintype "passive"))
    )
    (net (code "55") (name "Net-(R17-Pad2)") (class "Default")
      (node (ref "R17") (pin "2") (pinfunction "2_2") (pintype "passive"))
      (node (ref "SJ6") (pin "1") (pinfunction "1_1") (pintype "passive"))
    )
    (net (code "56") (name "Net-(R18-Pad2)") (class "Default")
      (node (ref "R18") (pin "2") (pinfunction "2_2") (pintype "passive"))
      (node (ref "SJ6") (pin "3") (pinfunction "3_3") (pintype "passive"))
    )
    (net (code "57") (name "Net-(R20-Pad1)") (class "Default")
      (node (ref "R20") (pin "1") (pinfunction "1_1") (pintype "passive"))
      (node (ref "SJ3") (pin "1") (pinfunction "1_1") (pintype "passive"))
    )
    (net (code "58") (name "Net-(R21-Pad1)") (class "Default")
      (node (ref "R21") (pin "1") (pinfunction "1_1") (pintype "passive"))
      (node (ref "SJ2") (pin "1") (pinfunction "1_1") (pintype "passive"))
    )
    (net (code "59") (name "Net-(U3-CHAN0)") (class "Default")
      (node (ref "SW1") (pin "20") (pinfunction "20_20") (pintype "passive"))
      (node (ref "U3") (pin "9") (pinfunction "CHAN0_9") (pintype "bidirectional"))
    )
    (net (code "60") (name "Net-(U3-CHAN1)") (class "Default")
      (node (ref "SW1") (pin "19") (pinfunction "19_19") (pintype "passive"))
      (node (ref "U3") (pin "8") (pinfunction "CHAN1_8") (pintype "bidirectional"))
    )
    (net (code "61") (name "Net-(U3-CHAN2)") (class "Default")
      (node (ref "SW1") (pin "18") (pinfunction "18_18") (pintype "passive"))
      (node (ref "U3") (pin "7") (pinfunction "CHAN2_7") (pintype "bidirectional"))
    )
    (net (code "62") (name "Net-(U3-CHAN3)") (class "Default")
      (node (ref "SW1") (pin "17") (pinfunction "17_17") (pintype "passive"))
      (node (ref "U3") (pin "6") (pinfunction "CHAN3_6") (pintype "bidirectional"))
    )
    (net (code "63") (name "Net-(U3-CHAN4)") (class "Default")
      (node (ref "SW1") (pin "16") (pinfunction "16_16") (pintype "passive"))
      (node (ref "U3") (pin "5") (pinfunction "CHAN4_5") (pintype "bidirectional"))
    )
    (net (code "64") (name "Net-(U3-CHAN5)") (class "Default")
      (node (ref "SW1") (pin "15") (pinfunction "15_15") (pintype "passive"))
      (node (ref "U3") (pin "4") (pinfunction "CHAN5_4") (pintype "bidirectional"))
    )
    (net (code "65") (name "Net-(U3-CHAN6)") (class "Default")
      (node (ref "SW1") (pin "14") (pinfunction "14_14") (pintype "passive"))
      (node (ref "U3") (pin "3") (pinfunction "CHAN6_3") (pintype "bidirectional"))
    )
    (net (code "66") (name "Net-(U3-CHAN7)") (class "Default")
      (node (ref "SW1") (pin "13") (pinfunction "13_13") (pintype "passive"))
      (node (ref "U3") (pin "2") (pinfunction "CHAN7_2") (pintype "bidirectional"))
    )
    (net (code "67") (name "Net-(U3-CHAN8)") (class "Default")
      (node (ref "SW1") (pin "12") (pinfunction "12_12") (pintype "passive"))
      (node (ref "U3") (pin "23") (pinfunction "CHAN8_23") (pintype "bidirectional"))
    )
    (net (code "68") (name "Net-(U3-CHAN9)") (class "Default")
      (node (ref "SW1") (pin "11") (pinfunction "11_11") (pintype "passive"))
      (node (ref "U3") (pin "22") (pinfunction "CHAN9_22") (pintype "bidirectional"))
    )
    (net (code "69") (name "OSCIO_SX1") (class "Default")
      (node (ref "U1") (pin "11") (pinfunction "OSCIO_11") (pintype "bidirectional"))
    )
    (net (code "70") (name "OSCIO_SX2") (class "Default")
      (node (ref "U2") (pin "11") (pinfunction "OSCIO_11") (pintype "bidirectional"))
    )
    (net (code "71") (name "PIN_2") (class "Default")
      (node (ref "CONN02") (pin "5") (pinfunction "5_5") (pintype "bidirectional"))
      (node (ref "R22") (pin "2") (pinfunction "2_2") (pintype "passive"))
      (node (ref "S2") (pin "3") (pinfunction "3_3") (pintype "passive"))
      (node (ref "S2") (pin "4") (pinfunction "4_4") (pintype "passive"))
    )
    (net (code "72") (name "SCL_01") (class "Default")
      (node (ref "CONN02") (pin "2") (pinfunction "2_2") (pintype "bidirectional"))
      (node (ref "R11") (pin "1") (pinfunction "1_1") (pintype "passive"))
      (node (ref "U1") (pin "25") (pinfunction "SCL_25") (pintype "bidirectional"))
    )
    (net (code "73") (name "SCL_02") (class "Default")
      (node (ref "CONN02") (pin "4") (pinfunction "4_4") (pintype "bidirectional"))
      (node (ref "R18") (pin "1") (pinfunction "1_1") (pintype "passive"))
      (node (ref "U2") (pin "25") (pinfunction "SCL_25") (pintype "bidirectional"))
    )
    (net (code "74") (name "SDA_01") (class "Default")
      (node (ref "CONN02") (pin "1") (pinfunction "1_1") (pintype "bidirectional"))
      (node (ref "R10") (pin "1") (pinfunction "1_1") (pintype "passive"))
      (node (ref "U1") (pin "24") (pinfunction "SDA_24") (pintype "bidirectional"))
    )
    (net (code "75") (name "SDA_02") (class "Default")
      (node (ref "CONN02") (pin "3") (pinfunction "3_3") (pintype "bidirectional"))
      (node (ref "R17") (pin "1") (pinfunction "1_1") (pintype "passive"))
      (node (ref "U2") (pin "24") (pinfunction "SDA_24") (pintype "bidirectional"))
    )
    (net (code "76") (name "VCC_5V") (class "Default")
      (node (ref "C3_LED") (pin "1") (pinfunction "1_1") (pintype "passive"))
      (node (ref "LED1") (pin "1-VDD") (pinfunction "VDD_1-VDD") (pintype "power_in"))
      (node (ref "M_01") (pin "2") (pinfunction "2_2") (pintype "passive"))
      (node (ref "M_02") (pin "2") (pinfunction "2_2") (pintype "passive"))
      (node (ref "M_03") (pin "2") (pinfunction "2_2") (pintype "passive"))
      (node (ref "M_04") (pin "2") (pinfunction "2_2") (pintype "passive"))
      (node (ref "M_05") (pin "2") (pinfunction "2_2") (pintype "passive"))
      (node (ref "M_06") (pin "2") (pinfunction "2_2") (pintype "passive"))
      (node (ref "M_07") (pin "2") (pinfunction "2_2") (pintype "passive"))
      (node (ref "M_08") (pin "2") (pinfunction "2_2") (pintype "passive"))
      (node (ref "U$1") (pin "P$3") (pinfunction "3_P$3") (pintype "bidirectional"))
    )
    (net (code "77") (name "VCC_5V_IN") (class "Default")
      (node (ref "CONN02") (pin "12") (pinfunction "12_12") (pintype "bidirectional"))
      (node (ref "U$1") (pin "P$2") (pinfunction "2_P$2") (pintype "bidirectional"))
    )
    (net (code "78") (name "unconnected-(LED1-DO-Pad2-DOUT)") (class "Default")
      (node (ref "LED1") (pin "2-DOUT") (pinfunction "DO_2-DOUT") (pintype "output"))
    )
    (net (code "79") (name "unconnected-(U$1-1-PadP$1)") (class "Default")
      (node (ref "U$1") (pin "P$1") (pinfunction "1_P$1") (pintype "bidirectional"))
    )
    (net (code "80") (name "unconnected-(U$1-4-PadP$4)") (class "Default")
      (node (ref "U$1") (pin "P$4") (pinfunction "4_P$4") (pintype "bidirectional"))
    )
    (net (code "81") (name "unconnected-(U$1-5-PadP$5)") (class "Default")
      (node (ref "U$1") (pin "P$5") (pinfunction "5_P$5") (pintype "bidirectional"))
    )
    (net (code "82") (name "unconnected-(U$1-6-PadP$6)") (class "Default")
      (node (ref "U$1") (pin "P$6") (pinfunction "6_P$6") (pintype "bidirectional"))
    )
    (net (code "83") (name "unconnected-(U3-CHAN10-Pad21)") (class "Default")
      (node (ref "U3") (pin "21") (pinfunction "CHAN10_21") (pintype "bidirectional"))
    )
    (net (code "84") (name "unconnected-(U3-CHAN11-Pad20)") (class "Default")
      (node (ref "U3") (pin "20") (pinfunction "CHAN11_20") (pintype "bidirectional"))
    )
    (net (code "85") (name "unconnected-(U3-CHAN12-Pad19)") (class "Default")
      (node (ref "U3") (pin "19") (pinfunction "CHAN12_19") (pintype "bidirectional"))
    )
    (net (code "86") (name "unconnected-(U3-CHAN13-Pad18)") (class "Default")
      (node (ref "U3") (pin "18") (pinfunction "CHAN13_18") (pintype "bidirectional"))
    )
    (net (code "87") (name "unconnected-(U3-CHAN14-Pad17)") (class "Default")
      (node (ref "U3") (pin "17") (pinfunction "CHAN14_17") (pintype "bidirectional"))
    )
    (net (code "88") (name "unconnected-(U3-CHAN15-Pad16)") (class "Default")
      (node (ref "U3") (pin "16") (pinfunction "CHAN15_16") (pintype "bidirectional"))
    )
  )
)
